# rapidshark-lipo-sensor-mk-1_1.net
KiCad netlist of a schematic drawn in EAGLE
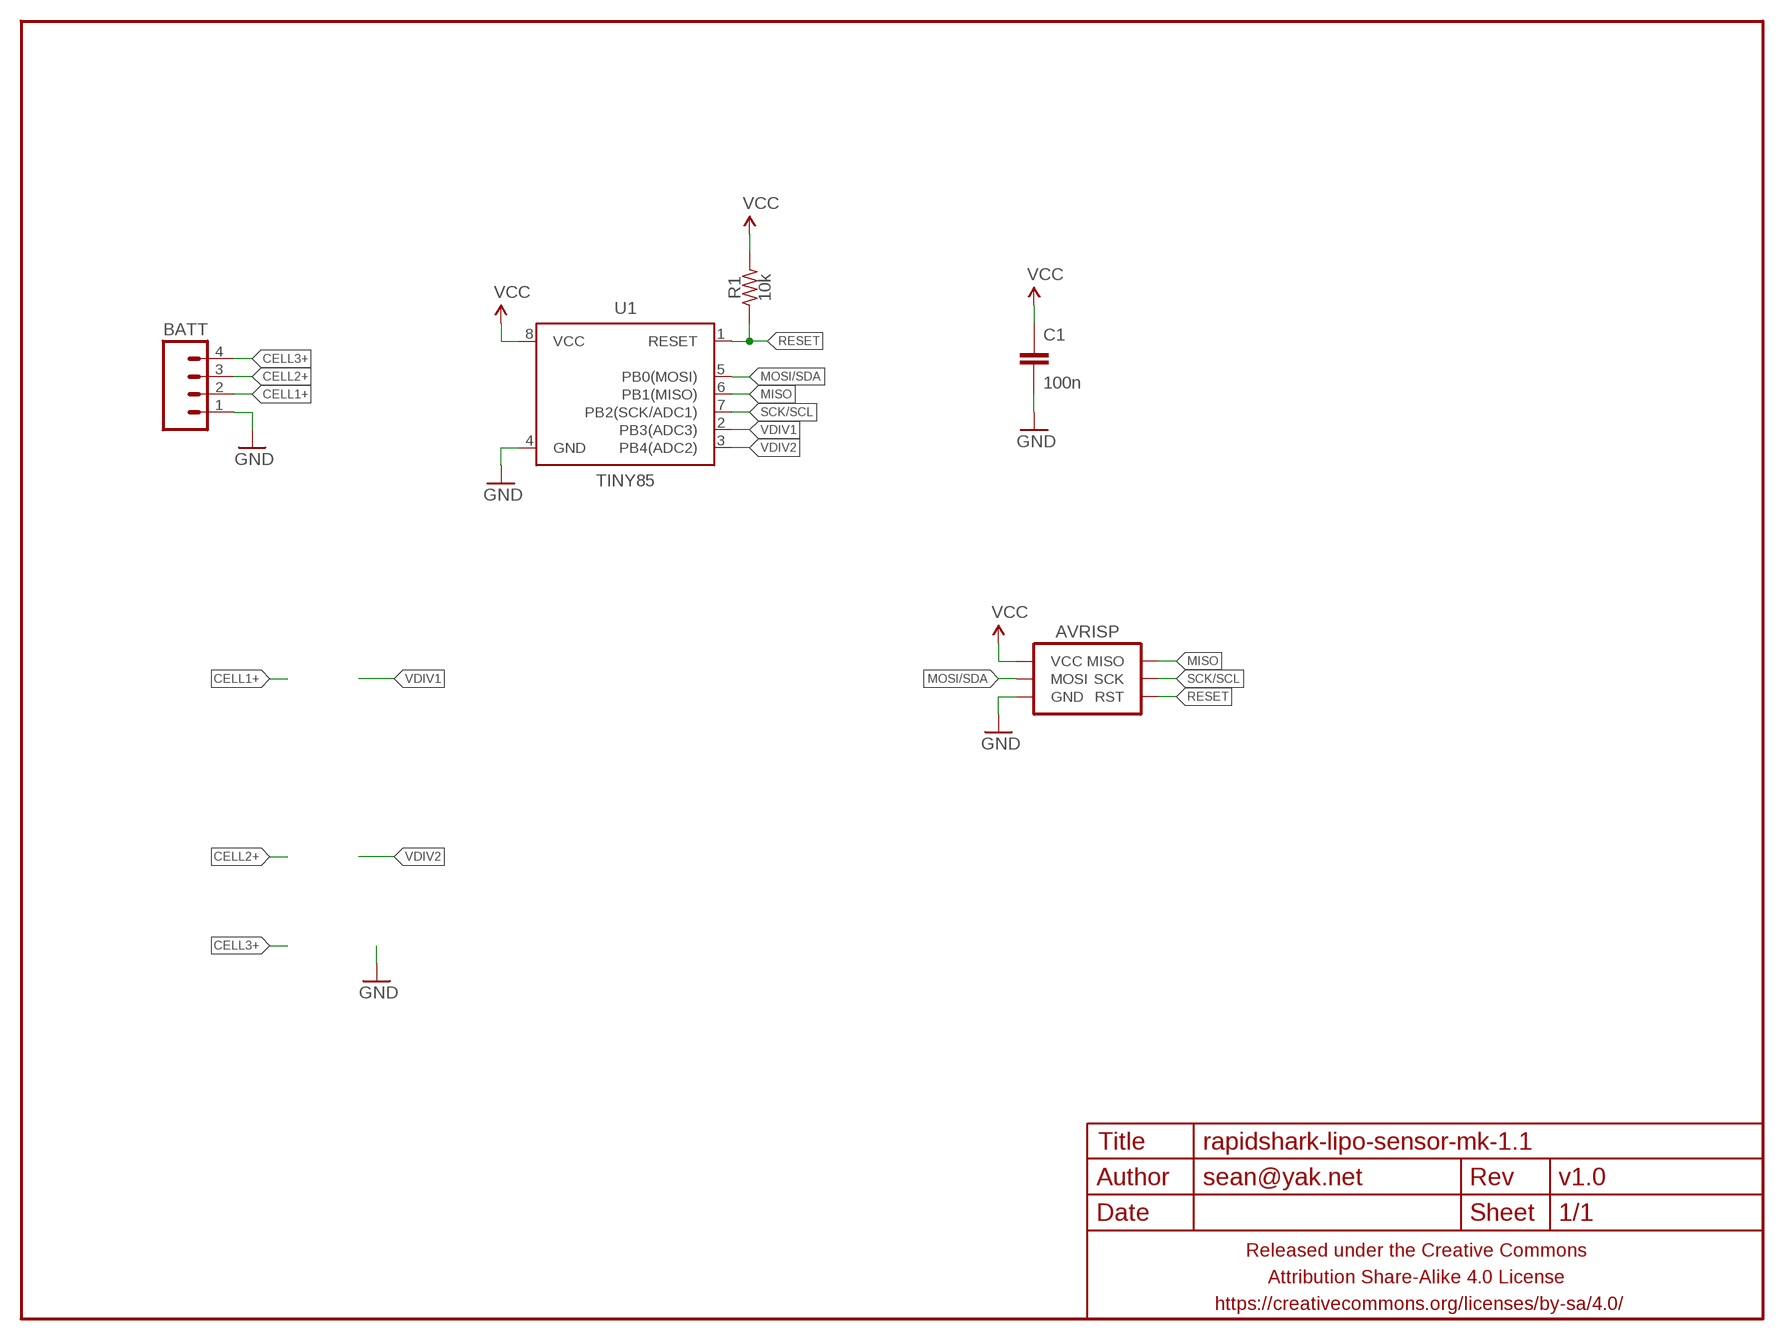
[diagram p0: schematic, sheet 1]

(export (version "E")
  (design (tool "Eeschema 10.0.6"))
  (components
    (comp (ref "AVRISP")
      (value "AVR_SPI_PRG_6PTH_INLINE_I2C")
      (footprint "eagle-import:AVR_ISP_INLINE_PTH_I2C")
      (libsource (lib "eagle-import") (part "AVR_SPI_PRG_6PTH_INLINE_I2C"))
    )
    (comp (ref "BATT")
      (value "M04JST_XH_VERT")
      (footprint "eagle-import:JST-4-XH-VERT-TH")
      (libsource (lib "eagle-import") (part "M04JST_XH_VERT"))
    )
    (comp (ref "C1")
      (value "100n")
      (footprint "eagle-import:C025-024X044")
      (libsource (lib "eagle-import") (part "CAPACITOR-CERAMIC025-024X044"))
    )
    (comp (ref "FRAME1")
      (value "FRAME-LETTERNO_PACKAGE")
      (footprint "eagle-import:DUMMY")
      (fields (field (name "DESIGNER") "sean@yak.net") (field (name "VERSION") "v1.0"))
      (libsource (lib "eagle-import") (part "FRAME-LETTERNO_PACKAGE"))
    )
    (comp (ref "R1")
      (value "10k")
      (footprint "eagle-import:RESISTOR-AXIAL-PTH-7.62MM")
      (libsource (lib "eagle-import") (part "RESISTORPTH-AXIAL-7.62MM"))
    )
    (comp (ref "U1")
      (value "TINY85")
      (footprint "eagle-import:DIP08")
      (libsource (lib "eagle-import") (part "ATTINY45TINY85-20-DIP"))
    )
  )
  (nets
    (net (code "1") (name "CELL1+") (class "Default")
      (node (ref "BATT") (pin "2") (pinfunction "2_2") (pintype "passive"))
    )
    (net (code "2") (name "CELL2+") (class "Default")
      (node (ref "BATT") (pin "3") (pinfunction "3_3") (pintype "passive"))
    )
    (net (code "3") (name "CELL3+") (class "Default")
      (node (ref "BATT") (pin "4") (pinfunction "4_4") (pintype "passive"))
    )
    (net (code "4") (name "GND") (class "Default")
      (node (ref "AVRISP") (pin "GND") (pinfunction "GND_GND") (pintype "passive"))
      (node (ref "BATT") (pin "1") (pinfunction "1_1") (pintype "passive"))
      (node (ref "C1") (pin "2") (pinfunction "2_2") (pintype "passive"))
      (node (ref "U1") (pin "4") (pinfunction "GND_4") (pintype "bidirectional"))
    )
    (net (code "5") (name "MISO") (class "Default")
      (node (ref "AVRISP") (pin "MISO") (pinfunction "MISO_MISO") (pintype "passive"))
      (node (ref "U1") (pin "6") (pinfunction "PB1(MISO)_6") (pintype "bidirectional"))
    )
    (net (code "6") (name "MOSI{slash}SDA") (class "Default")
      (node (ref "AVRISP") (pin "MOSI") (pinfunction "MOSI_MOSI") (pintype "passive"))
      (node (ref "U1") (pin "5") (pinfunction "PB0(MOSI)_5") (pintype "bidirectional"))
    )
    (net (code "7") (name "RESET") (class "Default")
      (node (ref "AVRISP") (pin "RESET") (pinfunction "RST_RESET") (pintype "passive"))
      (node (ref "R1") (pin "P$1") (pinfunction "1_P$1") (pintype "passive"))
      (node (ref "U1") (pin "1") (pinfunction "RESET_1") (pintype "bidirectional"))
    )
    (net (code "8") (name "SCK{slash}SCL") (class "Default")
      (node (ref "AVRISP") (pin "SCK") (pinfunction "SCK_SCK") (pintype "passive"))
      (node (ref "U1") (pin "7") (pinfunction "PB2(SCK/ADC1)_7") (pintype "bidirectional"))
    )
    (net (code "9") (name "VCC") (class "Default")
      (node (ref "AVRISP") (pin "VCC") (pinfunction "VCC_VCC") (pintype "passive"))
      (node (ref "C1") (pin "1") (pinfunction "1_1") (pintype "passive"))
      (node (ref "R1") (pin "P$2") (pinfunction "2_P$2") (pintype "passive"))
      (node (ref "U1") (pin "8") (pinfunction "VCC_8") (pintype "bidirectional"))
    )
    (net (code "10") (name "VDIV1") (class "Default")
      (node (ref "U1") (pin "2") (pinfunction "PB3(ADC3)_2") (pintype "bidirectional"))
    )
    (net (code "11") (name "VDIV2") (class "Default")
      (node (ref "U1") (pin "3") (pinfunction "PB4(ADC2)_3") (pintype "bidirectional"))
    )
  )
)
